# Sheet1.net
KiCad netlist of a schematic drawn in Altium Designer
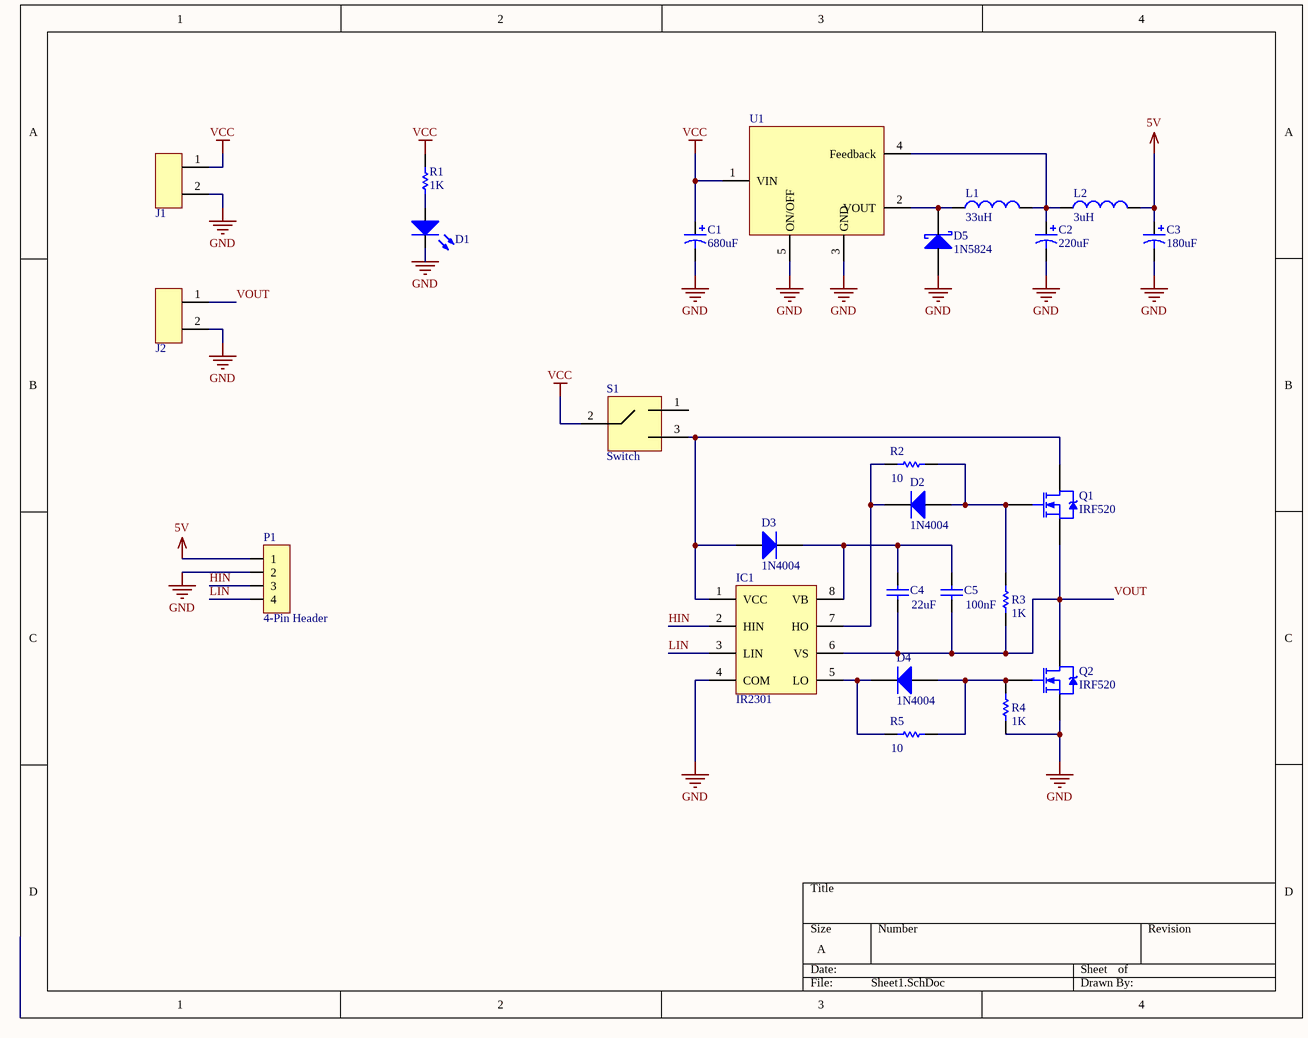
[diagram p0: Sheet1.SchDoc]

(export (version "E")
  (design (tool "Eeschema 10.0.6"))
  (components
    (comp (ref "C1")
      (value "680uF")
      (footprint "EEU-FM1V681")
      (description "Polarized Capacitor (Radial)")
      (fields (field (name "Comment") "Cap Pol1") (field (name "PUBLISHER") "Altium Limited"))
      (libsource (lib "Miscellaneous Devices") (part "Cap Pol1"))
    )
    (comp (ref "C2")
      (value "220uF")
      (footprint "EEU-FM1V221L")
      (description "Polarized Capacitor (Radial)")
      (fields (field (name "Comment") "Cap Pol1") (field (name "PUBLISHER") "Altium Limited"))
      (libsource (lib "Miscellaneous Devices") (part "Cap Pol1"))
    )
    (comp (ref "C3")
      (value "180uF")
      (footprint "EEU-FR1V181")
      (description "Polarized Capacitor (Radial)")
      (fields (field (name "Comment") "Cap Pol1") (field (name "PUBLISHER") "Altium Limited"))
      (libsource (lib "Miscellaneous Devices") (part "Cap Pol1"))
    )
    (comp (ref "C4")
      (value "22uF")
      (footprint "Axial Cap 0.5mm")
      (description "Capacitor")
      (fields (field (name "Comment") "Cap") (field (name "PUBLISHER") "Altium Limited"))
      (libsource (lib "Miscellaneous Devices") (part "Cap"))
    )
    (comp (ref "C5")
      (value "100nF")
      (footprint "Axial Cap 0.5mm")
      (description "Capacitor")
      (fields (field (name "Comment") "Cap") (field (name "PUBLISHER") "Altium Limited"))
      (libsource (lib "Miscellaneous Devices") (part "Cap"))
    )
    (comp (ref "D1")
      (value "LED")
      (footprint "RAD-0.1")
      (description "Generic LED")
      (libsource (lib "AltiumWorkshopBasic") (part "LED"))
    )
    (comp (ref "D2")
      (value "1N4004")
      (footprint "DO-41")
      (description "1 Amp General Purpose Rectifier")
      (fields (field (name "PUBLISHER") "Altium Limited"))
      (libsource (lib "Miscellaneous Devices") (part "Diode 1N4004"))
    )
    (comp (ref "D3")
      (value "1N4004")
      (footprint "DO-41")
      (description "1 Amp General Purpose Rectifier")
      (fields (field (name "PUBLISHER") "Altium Limited"))
      (libsource (lib "Miscellaneous Devices") (part "Diode 1N4004"))
    )
    (comp (ref "D4")
      (value "1N4004")
      (footprint "DO-41")
      (description "1 Amp General Purpose Rectifier")
      (fields (field (name "PUBLISHER") "Altium Limited"))
      (libsource (lib "Miscellaneous Devices") (part "Diode 1N4004"))
    )
    (comp (ref "D5")
      (value "1N5824")
      (footprint "DO-201AD")
      (libsource (lib "GrandPrieeeSch") (part "Schottky Diode"))
    )
    (comp (ref "IC1")
      (value "IR2301")
      (footprint "DIP-8")
      (description "High and Low Side Driver")
      (libsource (lib "AltiumWorkshopBasic") (part "IR2301"))
    )
    (comp (ref "J1")
      (value "Screw Terminal")
      (footprint "ST-2")
      (description "2 Port Screw Terminal")
      (libsource (lib "GrandPrieeeSch") (part "Screw Terminal"))
    )
    (comp (ref "J2")
      (value "Screw Terminal")
      (footprint "ST-2")
      (description "2 Port Screw Terminal")
      (libsource (lib "GrandPrieeeSch") (part "Screw Terminal"))
    )
    (comp (ref "L1")
      (value "33uH")
      (footprint "Inductor 2307-V-RC")
      (description "Inductor")
      (fields (field (name "PUBLISHER") "Altium Limited"))
      (libsource (lib "Miscellaneous Devices") (part "Inductor"))
    )
    (comp (ref "L2")
      (value "3uH")
      (footprint "Inductor Dia: 8.8mm")
      (description "Inductor")
      (fields (field (name "PUBLISHER") "Altium Limited"))
      (libsource (lib "Miscellaneous Devices") (part "Inductor"))
    )
    (comp (ref "P1")
      (value "4-Pin Header")
      (footprint "HDR-4P")
      (libsource (lib "AltiumWorkshopBasic") (part "HDR_1x4"))
    )
    (comp (ref "Q1")
      (value "IRF520")
      (footprint "TO-220AB")
      (description "N-Channel Power MOSFET")
      (fields (field (name "PUBLISHER") "Altium Limited"))
      (libsource (lib "Miscellaneous Devices") (part "NMOS-2"))
    )
    (comp (ref "Q2")
      (value "IRF520")
      (footprint "TO-220AB")
      (description "N-Channel Power MOSFET")
      (fields (field (name "PUBLISHER") "Altium Limited"))
      (libsource (lib "Miscellaneous Devices") (part "NMOS-2"))
    )
    (comp (ref "R1")
      (value "Resistor")
      (footprint "AXIAL-0.3")
      (description "Generic Resistor")
      (fields (field (name "RESISTANCE") "1K"))
      (libsource (lib "AltiumWorkshopBasic") (part "Resistor"))
    )
    (comp (ref "R2")
      (value "10")
      (footprint "AXIAL-0.3")
      (description "Resistor")
      (fields (field (name "Comment") "Res1") (field (name "PUBLISHER") "Altium Limited"))
      (libsource (lib "Miscellaneous Devices") (part "Res1"))
    )
    (comp (ref "R3")
      (value "1K")
      (footprint "AXIAL-0.3")
      (description "Resistor")
      (fields (field (name "Comment") "Res1") (field (name "PUBLISHER") "Altium Limited"))
      (libsource (lib "Miscellaneous Devices") (part "Res1"))
    )
    (comp (ref "R4")
      (value "1K")
      (footprint "AXIAL-0.3")
      (description "Resistor")
      (fields (field (name "Comment") "Res1") (field (name "PUBLISHER") "Altium Limited"))
      (libsource (lib "Miscellaneous Devices") (part "Res1"))
    )
    (comp (ref "R5")
      (value "10")
      (footprint "AXIAL-0.3")
      (description "Resistor")
      (fields (field (name "Comment") "Res1") (field (name "PUBLISHER") "Altium Limited"))
      (libsource (lib "Miscellaneous Devices") (part "Res1"))
    )
    (comp (ref "S1")
      (value "Switch")
      (footprint "E101 Switch")
      (libsource (lib "GrandPrieeeSch") (part "Switch"))
    )
    (comp (ref "U1")
      (value "Step-down switching regulator")
      (footprint "TO-220-5")
      (libsource (lib "AltiumWorkshopBasic") (part "LM2596"))
    )
  )
  (nets
    (net (code "1") (name "/HIN") (class "Default")
      (node (ref "IC1") (pin "2") (pinfunction "HIN_2") (pintype "passive"))
      (node (ref "P1") (pin "3") (pinfunction "3_3") (pintype "passive"))
    )
    (net (code "2") (name "/LIN") (class "Default")
      (node (ref "IC1") (pin "3") (pinfunction "LIN_3") (pintype "passive"))
      (node (ref "P1") (pin "4") (pinfunction "4_4") (pintype "passive"))
    )
    (net (code "3") (name "/VOUT") (class "Default")
      (node (ref "C4") (pin "1") (pinfunction "1_1") (pintype "passive"))
      (node (ref "C5") (pin "1") (pinfunction "1_1") (pintype "passive"))
      (node (ref "IC1") (pin "6") (pinfunction "VS_6") (pintype "passive"))
      (node (ref "J2") (pin "1") (pinfunction "1_1") (pintype "passive"))
      (node (ref "Q1") (pin "3") (pinfunction "S_3") (pintype "passive"))
      (node (ref "Q2") (pin "2") (pinfunction "D_2") (pintype "passive"))
      (node (ref "R3") (pin "1") (pinfunction "1_1") (pintype "passive"))
    )
    (net (code "4") (name "5V") (class "Default")
      (node (ref "C3") (pin "1") (pinfunction "1_1") (pintype "passive"))
      (node (ref "L2") (pin "2") (pinfunction "2_2") (pintype "passive"))
      (node (ref "P1") (pin "1") (pinfunction "1_1") (pintype "passive"))
    )
    (net (code "5") (name "GND") (class "Default")
      (node (ref "C1") (pin "2") (pinfunction "2_2") (pintype "passive"))
      (node (ref "C2") (pin "2") (pinfunction "2_2") (pintype "passive"))
      (node (ref "C3") (pin "2") (pinfunction "2_2") (pintype "passive"))
      (node (ref "D1") (pin "2") (pinfunction "K_2") (pintype "passive"))
      (node (ref "D5") (pin "2") (pinfunction "10_2") (pintype "passive"))
      (node (ref "IC1") (pin "4") (pinfunction "COM_4") (pintype "passive"))
      (node (ref "J1") (pin "2") (pinfunction "2_2") (pintype "passive"))
      (node (ref "J2") (pin "2") (pinfunction "2_2") (pintype "passive"))
      (node (ref "P1") (pin "2") (pinfunction "2_2") (pintype "passive"))
      (node (ref "Q2") (pin "3") (pinfunction "S_3") (pintype "passive"))
      (node (ref "R4") (pin "1") (pinfunction "1_1") (pintype "passive"))
      (node (ref "U1") (pin "3") (pinfunction "GND_3") (pintype "passive"))
      (node (ref "U1") (pin "5") (pinfunction "ON/OFF_5") (pintype "passive"))
    )
    (net (code "6") (name "Net-(D1-A)") (class "Default")
      (node (ref "D1") (pin "1") (pinfunction "A_1") (pintype "passive"))
      (node (ref "R1") (pin "1") (pinfunction "1_1") (pintype "passive"))
    )
    (net (code "7") (name "Net-(D2-A)") (class "Default")
      (node (ref "D2") (pin "1") (pinfunction "A_1") (pintype "passive"))
      (node (ref "Q1") (pin "1") (pinfunction "G_1") (pintype "passive"))
      (node (ref "R2") (pin "2") (pinfunction "2_2") (pintype "passive"))
      (node (ref "R3") (pin "2") (pinfunction "2_2") (pintype "passive"))
    )
    (net (code "8") (name "Net-(D2-K)") (class "Default")
      (node (ref "D2") (pin "2") (pinfunction "K_2") (pintype "passive"))
      (node (ref "IC1") (pin "7") (pinfunction "HO_7") (pintype "passive"))
      (node (ref "R2") (pin "1") (pinfunction "1_1") (pintype "passive"))
    )
    (net (code "9") (name "Net-(D3-A)") (class "Default")
      (node (ref "D3") (pin "1") (pinfunction "A_1") (pintype "passive"))
      (node (ref "IC1") (pin "1") (pinfunction "VCC_1") (pintype "passive"))
      (node (ref "Q1") (pin "2") (pinfunction "D_2") (pintype "passive"))
      (node (ref "S1") (pin "3") (pinfunction "OUT_3") (pintype "passive"))
    )
    (net (code "10") (name "Net-(D3-K)") (class "Default")
      (node (ref "C4") (pin "2") (pinfunction "2_2") (pintype "passive"))
      (node (ref "C5") (pin "2") (pinfunction "2_2") (pintype "passive"))
      (node (ref "D3") (pin "2") (pinfunction "K_2") (pintype "passive"))
      (node (ref "IC1") (pin "8") (pinfunction "VB_8") (pintype "passive"))
    )
    (net (code "11") (name "Net-(D4-A)") (class "Default")
      (node (ref "D4") (pin "1") (pinfunction "A_1") (pintype "passive"))
      (node (ref "Q2") (pin "1") (pinfunction "G_1") (pintype "passive"))
      (node (ref "R4") (pin "2") (pinfunction "2_2") (pintype "passive"))
      (node (ref "R5") (pin "2") (pinfunction "2_2") (pintype "passive"))
    )
    (net (code "12") (name "Net-(D4-K)") (class "Default")
      (node (ref "D4") (pin "2") (pinfunction "K_2") (pintype "passive"))
      (node (ref "IC1") (pin "5") (pinfunction "LO_5") (pintype "passive"))
      (node (ref "R5") (pin "1") (pinfunction "1_1") (pintype "passive"))
    )
    (net (code "13") (name "Net-(D5-11)") (class "Default")
      (node (ref "D5") (pin "1") (pinfunction "11_1") (pintype "passive"))
      (node (ref "L1") (pin "1") (pinfunction "1_1") (pintype "passive"))
      (node (ref "U1") (pin "2") (pinfunction "VOUT_2") (pintype "passive"))
    )
    (net (code "14") (name "Net-(U1-Feedback)") (class "Default")
      (node (ref "C2") (pin "1") (pinfunction "1_1") (pintype "passive"))
      (node (ref "L1") (pin "2") (pinfunction "2_2") (pintype "passive"))
      (node (ref "L2") (pin "1") (pinfunction "1_1") (pintype "passive"))
      (node (ref "U1") (pin "4") (pinfunction "Feedback_4") (pintype "passive"))
    )
    (net (code "15") (name "VCC") (class "Default")
      (node (ref "C1") (pin "1") (pinfunction "1_1") (pintype "passive"))
      (node (ref "J1") (pin "1") (pinfunction "1_1") (pintype "passive"))
      (node (ref "R1") (pin "2") (pinfunction "2_2") (pintype "passive"))
      (node (ref "S1") (pin "2") (pinfunction "IN_2") (pintype "passive"))
      (node (ref "U1") (pin "1") (pinfunction "VIN_1") (pintype "passive"))
    )
    (net (code "16") (name "unconnected-(S1-OUT-Pad1)") (class "Default")
      (node (ref "S1") (pin "1") (pinfunction "OUT_1") (pintype "passive"))
    )
  )
)
